# LTM8056.net
KiCad netlist of a schematic drawn in Altium Designer
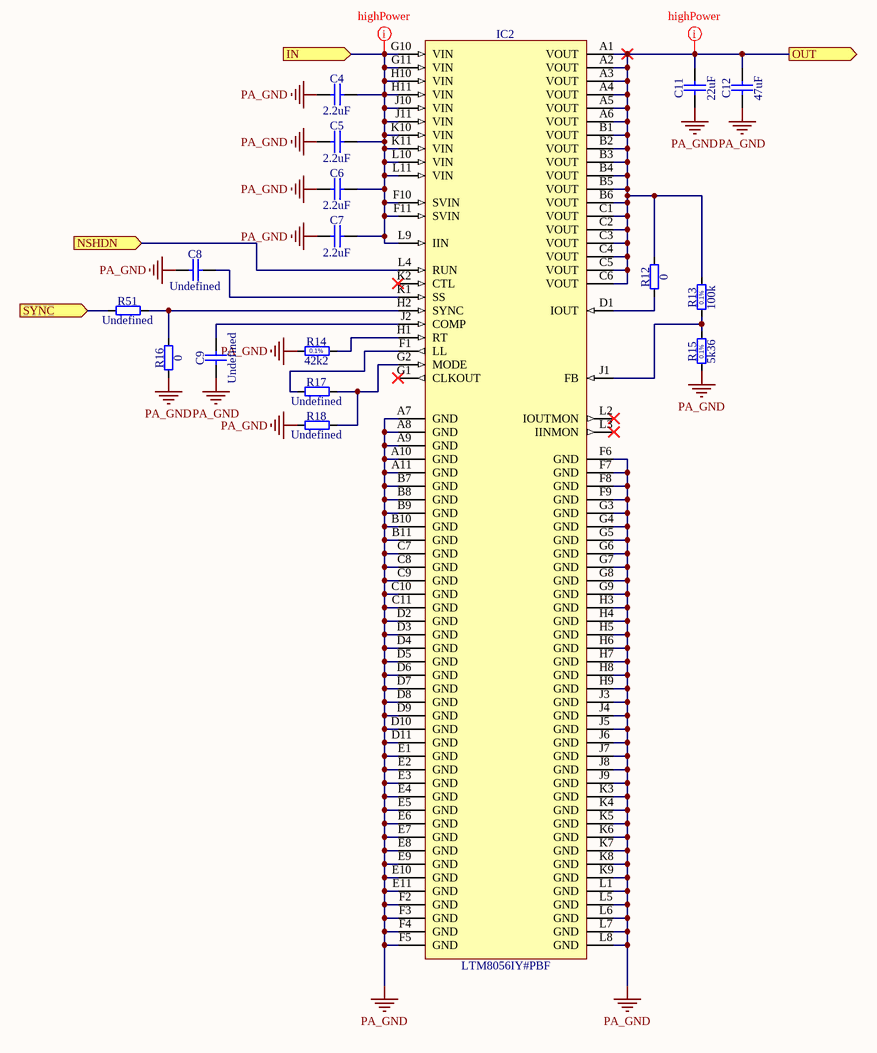
[diagram p0: LTM8056.SchDoc]

(export (version "E")
  (design (tool "Eeschema 10.0.6"))
  (components
    (comp (ref "C4")
      (value "2.2uF")
      (footprint "CAPC3216X180N")
      (description "Non-polarised capacitor")
      (fields
        (field (name "PART NUMBER") "CC1206_2.2UF_50V_10%_X7R")
        (field (name "VOLTAGE") "50V")
        (field (name "AUTHOR") "CERN DEM MR")
      )
      (libsource (lib "Capacitors") (part "Capacitor - non polarized"))
    )
    (comp (ref "C5")
      (value "2.2uF")
      (footprint "CAPC3216X180N")
      (description "Non-polarised capacitor")
      (fields
        (field (name "PART NUMBER") "CC1206_2.2UF_50V_10%_X7R")
        (field (name "VOLTAGE") "50V")
        (field (name "AUTHOR") "CERN DEM MR")
      )
      (libsource (lib "Capacitors") (part "Capacitor - non polarized"))
    )
    (comp (ref "C6")
      (value "2.2uF")
      (footprint "CAPC3216X180N")
      (description "Non-polarised capacitor")
      (fields
        (field (name "PART NUMBER") "CC1206_2.2UF_50V_10%_X7R")
        (field (name "VOLTAGE") "50V")
        (field (name "AUTHOR") "CERN DEM MR")
      )
      (libsource (lib "Capacitors") (part "Capacitor - non polarized"))
    )
    (comp (ref "C7")
      (value "2.2uF")
      (footprint "CAPC3216X180N")
      (description "Non-polarised capacitor")
      (fields
        (field (name "PART NUMBER") "CC1206_2.2UF_50V_10%_X7R")
        (field (name "VOLTAGE") "50V")
        (field (name "AUTHOR") "CERN DEM MR")
      )
      (libsource (lib "Capacitors") (part "Capacitor - non polarized"))
    )
    (comp (ref "C8")
      (value "Undefined")
      (footprint "CAPC1608X90N")
      (description "Non-polarised capacitor")
      (fields (field (name "PART NUMBER") "CC0603_NO-VALUE") (field (name "AUTHOR") "CERN DEM MR"))
      (libsource (lib "Capacitors") (part "Capacitor - non polarized"))
    )
    (comp (ref "C9")
      (value "Undefined")
      (footprint "CAPC1608X90N")
      (description "Non-polarised capacitor")
      (fields (field (name "PART NUMBER") "CC0603_NO-VALUE") (field (name "AUTHOR") "CERN DEM MR"))
      (libsource (lib "Capacitors") (part "Capacitor - non polarized"))
    )
    (comp (ref "C11")
      (value "22uF")
      (footprint "CAPC_KEMET_KPS2220")
      (description "Non-polarised capacitor")
      (fields
        (field (name "PART NUMBER") "CC2220_22UF_50V_20%_X7R_KEMET_KPS")
        (field (name "VOLTAGE") "50V")
        (field (name "AUTHOR") "CERN DEM JLC")
      )
      (libsource (lib "Capacitors") (part "Capacitor - non polarized"))
    )
    (comp (ref "C12")
      (value "47uF")
      (footprint "CAPC_TDK_CKG57N")
      (description "Non-polarised capacitor")
      (fields
        (field (name "PART NUMBER") "CC2220_47UF_25V_20%_X7S_TDK_CKG57N")
        (field (name "VOLTAGE") "25V")
        (field (name "AUTHOR") "CERN DEM JLC")
      )
      (libsource (lib "Capacitors") (part "Capacitor - non polarized"))
    )
    (comp (ref "IC2")
      (value "LTM8056IY#PBF")
      (footprint "BGA121C127P11X11_1500X1500X512")
      (description "58VIN, 48VOUT Buck-Boost µModule Regulator")
      (fields (field (name "MANUFACTURER") "LINEAR TECHNOLOGY") (field (name "AUTHOR") "CERN DEM JLC"))
      (libsource (lib "ICs And Semiconductors") (part "LTM8056"))
    )
    (comp (ref "R12")
      (value "0")
      (footprint "RESC1608X55N")
      (description "Resistor")
      (fields
        (field (name "PART NUMBER") "R0603_0R_JUMPER")
        (field (name "MANUFACTURER") "GENERIC")
        (field (name "AUTHOR") "CERN DEM JLC")
      )
      (libsource (lib "Resistors") (part "Resistor"))
    )
    (comp (ref "R13")
      (value "100k")
      (footprint "RESC1608X55N")
      (description "Resistor - 0.1%")
      (fields
        (field (name "PART NUMBER") "R0603_100K_0.1%_0.063W_10PPM")
        (field (name "POWER") "0.063W")
        (field (name "AUTHOR") "CERN DEM JLC")
      )
      (libsource (lib "Resistors") (part "Resistor - 0.1%"))
    )
    (comp (ref "R14")
      (value "42k2")
      (footprint "RESC1608X55N")
      (description "Resistor - 0.1%")
      (fields
        (field (name "PART NUMBER") "R0603_42K2_0.1%_0.063W_10PPM")
        (field (name "POWER") "0.063W")
        (field (name "AUTHOR") "CERN DEM JLC")
      )
      (libsource (lib "Resistors") (part "Resistor - 0.1%"))
    )
    (comp (ref "R15")
      (value "5k36")
      (footprint "RESC1608X55N")
      (description "Resistor - 0.1%")
      (fields
        (field (name "PART NUMBER") "R0603_5K36_0.1%_0.063W_10PPM")
        (field (name "POWER") "0.063W")
        (field (name "AUTHOR") "CERN DEM JLC")
      )
      (libsource (lib "Resistors") (part "Resistor - 0.1%"))
    )
    (comp (ref "R16")
      (value "0")
      (footprint "RESC1608X55N")
      (description "Resistor")
      (fields
        (field (name "PART NUMBER") "R0603_0R_JUMPER")
        (field (name "MANUFACTURER") "GENERIC")
        (field (name "AUTHOR") "CERN DEM JLC")
      )
      (libsource (lib "Resistors") (part "Resistor"))
    )
    (comp (ref "R17")
      (value "Undefined")
      (footprint "RESC1608X55N")
      (description "Resistor")
      (fields (field (name "PART NUMBER") "R0603_NO-VALUE") (field (name "AUTHOR") "CERN DEM JLC"))
      (libsource (lib "Resistors") (part "Resistor"))
    )
    (comp (ref "R18")
      (value "Undefined")
      (footprint "RESC1608X55N")
      (description "Resistor")
      (fields (field (name "PART NUMBER") "R0603_NO-VALUE") (field (name "AUTHOR") "CERN DEM JLC"))
      (libsource (lib "Resistors") (part "Resistor"))
    )
    (comp (ref "R51")
      (value "Undefined")
      (footprint "RESC1608X55N")
      (description "Resistor")
      (fields (field (name "PART NUMBER") "R0603_NO-VALUE") (field (name "AUTHOR") "CERN DEM JLC"))
      (libsource (lib "Resistors") (part "Resistor"))
    )
  )
  (nets
    (net (code "1") (name "/IN") (class "Default")
      (node (ref "C4") (pin "2") (pinfunction "2_2") (pintype "passive"))
      (node (ref "C5") (pin "2") (pinfunction "2_2") (pintype "passive"))
      (node (ref "C6") (pin "2") (pinfunction "2_2") (pintype "passive"))
      (node (ref "C7") (pin "2") (pinfunction "2_2") (pintype "passive"))
      (node (ref "IC2") (pin "F10") (pinfunction "SVIN_F10") (pintype "input"))
      (node (ref "IC2") (pin "F11") (pinfunction "SVIN_F11") (pintype "input"))
      (node (ref "IC2") (pin "G10") (pinfunction "VIN_G10") (pintype "input"))
      (node (ref "IC2") (pin "G11") (pinfunction "VIN_G11") (pintype "input"))
      (node (ref "IC2") (pin "H10") (pinfunction "VIN_H10") (pintype "input"))
      (node (ref "IC2") (pin "H11") (pinfunction "VIN_H11") (pintype "input"))
      (node (ref "IC2") (pin "J10") (pinfunction "VIN_J10") (pintype "input"))
      (node (ref "IC2") (pin "J11") (pinfunction "VIN_J11") (pintype "input"))
      (node (ref "IC2") (pin "K10") (pinfunction "VIN_K10") (pintype "input"))
      (node (ref "IC2") (pin "K11") (pinfunction "VIN_K11") (pintype "input"))
      (node (ref "IC2") (pin "L10") (pinfunction "VIN_L10") (pintype "input"))
      (node (ref "IC2") (pin "L11") (pinfunction "VIN_L11") (pintype "input"))
      (node (ref "IC2") (pin "L9") (pinfunction "IIN_L9") (pintype "input"))
    )
    (net (code "2") (name "/NSHDN") (class "Default")
      (node (ref "IC2") (pin "L4") (pinfunction "RUN_L4") (pintype "input"))
    )
    (net (code "3") (name "/OUT") (class "Default")
      (node (ref "C11") (pin "2") (pinfunction "2_2") (pintype "passive"))
      (node (ref "C12") (pin "2") (pinfunction "2_2") (pintype "passive"))
      (node (ref "IC2") (pin "A1") (pinfunction "VOUT_A1") (pintype "power_in"))
      (node (ref "IC2") (pin "A2") (pinfunction "VOUT_A2") (pintype "power_in"))
      (node (ref "IC2") (pin "A3") (pinfunction "VOUT_A3") (pintype "power_in"))
      (node (ref "IC2") (pin "A4") (pinfunction "VOUT_A4") (pintype "power_in"))
      (node (ref "IC2") (pin "A5") (pinfunction "VOUT_A5") (pintype "power_in"))
      (node (ref "IC2") (pin "A6") (pinfunction "VOUT_A6") (pintype "power_in"))
      (node (ref "IC2") (pin "B1") (pinfunction "VOUT_B1") (pintype "power_in"))
      (node (ref "IC2") (pin "B2") (pinfunction "VOUT_B2") (pintype "power_in"))
      (node (ref "IC2") (pin "B3") (pinfunction "VOUT_B3") (pintype "power_in"))
      (node (ref "IC2") (pin "B4") (pinfunction "VOUT_B4") (pintype "power_in"))
      (node (ref "IC2") (pin "B5") (pinfunction "VOUT_B5") (pintype "power_in"))
      (node (ref "IC2") (pin "B6") (pinfunction "VOUT_B6") (pintype "power_in"))
      (node (ref "IC2") (pin "C1") (pinfunction "VOUT_C1") (pintype "power_in"))
      (node (ref "IC2") (pin "C2") (pinfunction "VOUT_C2") (pintype "power_in"))
      (node (ref "IC2") (pin "C3") (pinfunction "VOUT_C3") (pintype "power_in"))
      (node (ref "IC2") (pin "C4") (pinfunction "VOUT_C4") (pintype "power_in"))
      (node (ref "IC2") (pin "C5") (pinfunction "VOUT_C5") (pintype "power_in"))
      (node (ref "IC2") (pin "C6") (pinfunction "VOUT_C6") (pintype "power_in"))
      (node (ref "R12") (pin "2") (pinfunction "2_2") (pintype "passive"))
      (node (ref "R13") (pin "2") (pinfunction "2_2") (pintype "passive"))
    )
    (net (code "4") (name "/SYNC") (class "Default")
      (node (ref "R51") (pin "1") (pinfunction "1_1") (pintype "passive"))
    )
    (net (code "5") (name "Net-(IC2-COMP)") (class "Default")
      (node (ref "C9") (pin "2") (pinfunction "2_2") (pintype "passive"))
      (node (ref "IC2") (pin "J2") (pinfunction "COMP_J2") (pintype "input"))
    )
    (net (code "6") (name "Net-(IC2-FB)") (class "Default")
      (node (ref "IC2") (pin "J1") (pinfunction "FB_J1") (pintype "input"))
      (node (ref "R13") (pin "1") (pinfunction "1_1") (pintype "passive"))
      (node (ref "R15") (pin "2") (pinfunction "2_2") (pintype "passive"))
    )
    (net (code "7") (name "Net-(IC2-IOUT)") (class "Default")
      (node (ref "IC2") (pin "D1") (pinfunction "IOUT_D1") (pintype "input"))
      (node (ref "R12") (pin "1") (pinfunction "1_1") (pintype "passive"))
    )
    (net (code "8") (name "Net-(IC2-LL)") (class "Default")
      (node (ref "IC2") (pin "F1") (pinfunction "LL_F1") (pintype "output"))
      (node (ref "R17") (pin "1") (pinfunction "1_1") (pintype "passive"))
    )
    (net (code "9") (name "Net-(IC2-MODE)") (class "Default")
      (node (ref "IC2") (pin "G2") (pinfunction "MODE_G2") (pintype "input"))
      (node (ref "R17") (pin "2") (pinfunction "2_2") (pintype "passive"))
      (node (ref "R18") (pin "2") (pinfunction "2_2") (pintype "passive"))
    )
    (net (code "10") (name "Net-(IC2-RT)") (class "Default")
      (node (ref "IC2") (pin "H1") (pinfunction "RT_H1") (pintype "input"))
      (node (ref "R14") (pin "2") (pinfunction "2_2") (pintype "passive"))
    )
    (net (code "11") (name "Net-(IC2-SS)") (class "Default")
      (node (ref "C8") (pin "2") (pinfunction "2_2") (pintype "passive"))
      (node (ref "IC2") (pin "K1") (pinfunction "SS_K1") (pintype "input"))
    )
    (net (code "12") (name "Net-(IC2-SYNC)") (class "Default")
      (node (ref "IC2") (pin "H2") (pinfunction "SYNC_H2") (pintype "input"))
      (node (ref "R16") (pin "2") (pinfunction "2_2") (pintype "passive"))
      (node (ref "R51") (pin "2") (pinfunction "2_2") (pintype "passive"))
    )
    (net (code "13") (name "PA_GND") (class "Default")
      (node (ref "C11") (pin "1") (pinfunction "1_1") (pintype "passive"))
      (node (ref "C12") (pin "1") (pinfunction "1_1") (pintype "passive"))
      (node (ref "C4") (pin "1") (pinfunction "1_1") (pintype "passive"))
      (node (ref "C5") (pin "1") (pinfunction "1_1") (pintype "passive"))
      (node (ref "C6") (pin "1") (pinfunction "1_1") (pintype "passive"))
      (node (ref "C7") (pin "1") (pinfunction "1_1") (pintype "passive"))
      (node (ref "C8") (pin "1") (pinfunction "1_1") (pintype "passive"))
      (node (ref "C9") (pin "1") (pinfunction "1_1") (pintype "passive"))
      (node (ref "IC2") (pin "A10") (pinfunction "GND_A10") (pintype "power_in"))
      (node (ref "IC2") (pin "A11") (pinfunction "GND_A11") (pintype "power_in"))
      (node (ref "IC2") (pin "A7") (pinfunction "GND_A7") (pintype "power_in"))
      (node (ref "IC2") (pin "A8") (pinfunction "GND_A8") (pintype "power_in"))
      (node (ref "IC2") (pin "A9") (pinfunction "GND_A9") (pintype "power_in"))
      (node (ref "IC2") (pin "B10") (pinfunction "GND_B10") (pintype "power_in"))
      (node (ref "IC2") (pin "B11") (pinfunction "GND_B11") (pintype "power_in"))
      (node (ref "IC2") (pin "B7") (pinfunction "GND_B7") (pintype "power_in"))
      (node (ref "IC2") (pin "B8") (pinfunction "GND_B8") (pintype "power_in"))
      (node (ref "IC2") (pin "B9") (pinfunction "GND_B9") (pintype "power_in"))
      (node (ref "IC2") (pin "C10") (pinfunction "GND_C10") (pintype "power_in"))
      (node (ref "IC2") (pin "C11") (pinfunction "GND_C11") (pintype "power_in"))
      (node (ref "IC2") (pin "C7") (pinfunction "GND_C7") (pintype "power_in"))
      (node (ref "IC2") (pin "C8") (pinfunction "GND_C8") (pintype "power_in"))
      (node (ref "IC2") (pin "C9") (pinfunction "GND_C9") (pintype "power_in"))
      (node (ref "IC2") (pin "D10") (pinfunction "GND_D10") (pintype "power_in"))
      (node (ref "IC2") (pin "D11") (pinfunction "GND_D11") (pintype "power_in"))
      (node (ref "IC2") (pin "D2") (pinfunction "GND_D2") (pintype "power_in"))
      (node (ref "IC2") (pin "D3") (pinfunction "GND_D3") (pintype "power_in"))
      (node (ref "IC2") (pin "D4") (pinfunction "GND_D4") (pintype "power_in"))
      (node (ref "IC2") (pin "D5") (pinfunction "GND_D5") (pintype "power_in"))
      (node (ref "IC2") (pin "D6") (pinfunction "GND_D6") (pintype "power_in"))
      (node (ref "IC2") (pin "D7") (pinfunction "GND_D7") (pintype "power_in"))
      (node (ref "IC2") (pin "D8") (pinfunction "GND_D8") (pintype "power_in"))
      (node (ref "IC2") (pin "D9") (pinfunction "GND_D9") (pintype "power_in"))
      (node (ref "IC2") (pin "E1") (pinfunction "GND_E1") (pintype "power_in"))
      (node (ref "IC2") (pin "E10") (pinfunction "GND_E10") (pintype "power_in"))
      (node (ref "IC2") (pin "E11") (pinfunction "GND_E11") (pintype "power_in"))
      (node (ref "IC2") (pin "E2") (pinfunction "GND_E2") (pintype "power_in"))
      (node (ref "IC2") (pin "E3") (pinfunction "GND_E3") (pintype "power_in"))
      (node (ref "IC2") (pin "E4") (pinfunction "GND_E4") (pintype "power_in"))
      (node (ref "IC2") (pin "E5") (pinfunction "GND_E5") (pintype "power_in"))
      (node (ref "IC2") (pin "E6") (pinfunction "GND_E6") (pintype "power_in"))
      (node (ref "IC2") (pin "E7") (pinfunction "GND_E7") (pintype "power_in"))
      (node (ref "IC2") (pin "E8") (pinfunction "GND_E8") (pintype "power_in"))
      (node (ref "IC2") (pin "E9") (pinfunction "GND_E9") (pintype "power_in"))
      (node (ref "IC2") (pin "F2") (pinfunction "GND_F2") (pintype "power_in"))
      (node (ref "IC2") (pin "F3") (pinfunction "GND_F3") (pintype "power_in"))
      (node (ref "IC2") (pin "F4") (pinfunction "GND_F4") (pintype "power_in"))
      (node (ref "IC2") (pin "F5") (pinfunction "GND_F5") (pintype "power_in"))
      (node (ref "IC2") (pin "F6") (pinfunction "GND_F6") (pintype "power_in"))
      (node (ref "IC2") (pin "F7") (pinfunction "GND_F7") (pintype "power_in"))
      (node (ref "IC2") (pin "F8") (pinfunction "GND_F8") (pintype "power_in"))
      (node (ref "IC2") (pin "F9") (pinfunction "GND_F9") (pintype "power_in"))
      (node (ref "IC2") (pin "G3") (pinfunction "GND_G3") (pintype "power_in"))
      (node (ref "IC2") (pin "G4") (pinfunction "GND_G4") (pintype "power_in"))
      (node (ref "IC2") (pin "G5") (pinfunction "GND_G5") (pintype "power_in"))
      (node (ref "IC2") (pin "G6") (pinfunction "GND_G6") (pintype "power_in"))
      (node (ref "IC2") (pin "G7") (pinfunction "GND_G7") (pintype "power_in"))
      (node (ref "IC2") (pin "G8") (pinfunction "GND_G8") (pintype "power_in"))
      (node (ref "IC2") (pin "G9") (pinfunction "GND_G9") (pintype "power_in"))
      (node (ref "IC2") (pin "H3") (pinfunction "GND_H3") (pintype "power_in"))
      (node (ref "IC2") (pin "H4") (pinfunction "GND_H4") (pintype "power_in"))
      (node (ref "IC2") (pin "H5") (pinfunction "GND_H5") (pintype "power_in"))
      (node (ref "IC2") (pin "H6") (pinfunction "GND_H6") (pintype "power_in"))
      (node (ref "IC2") (pin "H7") (pinfunction "GND_H7") (pintype "power_in"))
      (node (ref "IC2") (pin "H8") (pinfunction "GND_H8") (pintype "power_in"))
      (node (ref "IC2") (pin "H9") (pinfunction "GND_H9") (pintype "power_in"))
      (node (ref "IC2") (pin "J3") (pinfunction "GND_J3") (pintype "power_in"))
      (node (ref "IC2") (pin "J4") (pinfunction "GND_J4") (pintype "power_in"))
      (node (ref "IC2") (pin "J5") (pinfunction "GND_J5") (pintype "power_in"))
      (node (ref "IC2") (pin "J6") (pinfunction "GND_J6") (pintype "power_in"))
      (node (ref "IC2") (pin "J7") (pinfunction "GND_J7") (pintype "power_in"))
      (node (ref "IC2") (pin "J8") (pinfunction "GND_J8") (pintype "power_in"))
      (node (ref "IC2") (pin "J9") (pinfunction "GND_J9") (pintype "power_in"))
      (node (ref "IC2") (pin "K3") (pinfunction "GND_K3") (pintype "power_in"))
      (node (ref "IC2") (pin "K4") (pinfunction "GND_K4") (pintype "power_in"))
      (node (ref "IC2") (pin "K5") (pinfunction "GND_K5") (pintype "power_in"))
      (node (ref "IC2") (pin "K6") (pinfunction "GND_K6") (pintype "power_in"))
      (node (ref "IC2") (pin "K7") (pinfunction "GND_K7") (pintype "power_in"))
      (node (ref "IC2") (pin "K8") (pinfunction "GND_K8") (pintype "power_in"))
      (node (ref "IC2") (pin "K9") (pinfunction "GND_K9") (pintype "power_in"))
      (node (ref "IC2") (pin "L1") (pinfunction "GND_L1") (pintype "power_in"))
      (node (ref "IC2") (pin "L5") (pinfunction "GND_L5") (pintype "power_in"))
      (node (ref "IC2") (pin "L6") (pinfunction "GND_L6") (pintype "power_in"))
      (node (ref "IC2") (pin "L7") (pinfunction "GND_L7") (pintype "power_in"))
      (node (ref "IC2") (pin "L8") (pinfunction "GND_L8") (pintype "power_in"))
      (node (ref "R14") (pin "1") (pinfunction "1_1") (pintype "passive"))
      (node (ref "R15") (pin "1") (pinfunction "1_1") (pintype "passive"))
      (node (ref "R16") (pin "1") (pinfunction "1_1") (pintype "passive"))
      (node (ref "R18") (pin "1") (pinfunction "1_1") (pintype "passive"))
    )
    (net (code "14") (name "unconnected-(IC2-CLKOUT-PadG1)") (class "Default")
      (node (ref "IC2") (pin "G1") (pinfunction "CLKOUT_G1") (pintype "output+no_connect"))
    )
    (net (code "15") (name "unconnected-(IC2-CTL-PadK2)") (class "Default")
      (node (ref "IC2") (pin "K2") (pinfunction "CTL_K2") (pintype "input+no_connect"))
    )
    (net (code "16") (name "unconnected-(IC2-IINMON-PadL3)") (class "Default")
      (node (ref "IC2") (pin "L3") (pinfunction "IINMON_L3") (pintype "output+no_connect"))
    )
    (net (code "17") (name "unconnected-(IC2-IOUTMON-PadL2)") (class "Default")
      (node (ref "IC2") (pin "L2") (pinfunction "IOUTMON_L2") (pintype "output+no_connect"))
    )
  )
)
